# olm-ec-periph.net
KiCad netlist of a schematic drawn in EAGLE
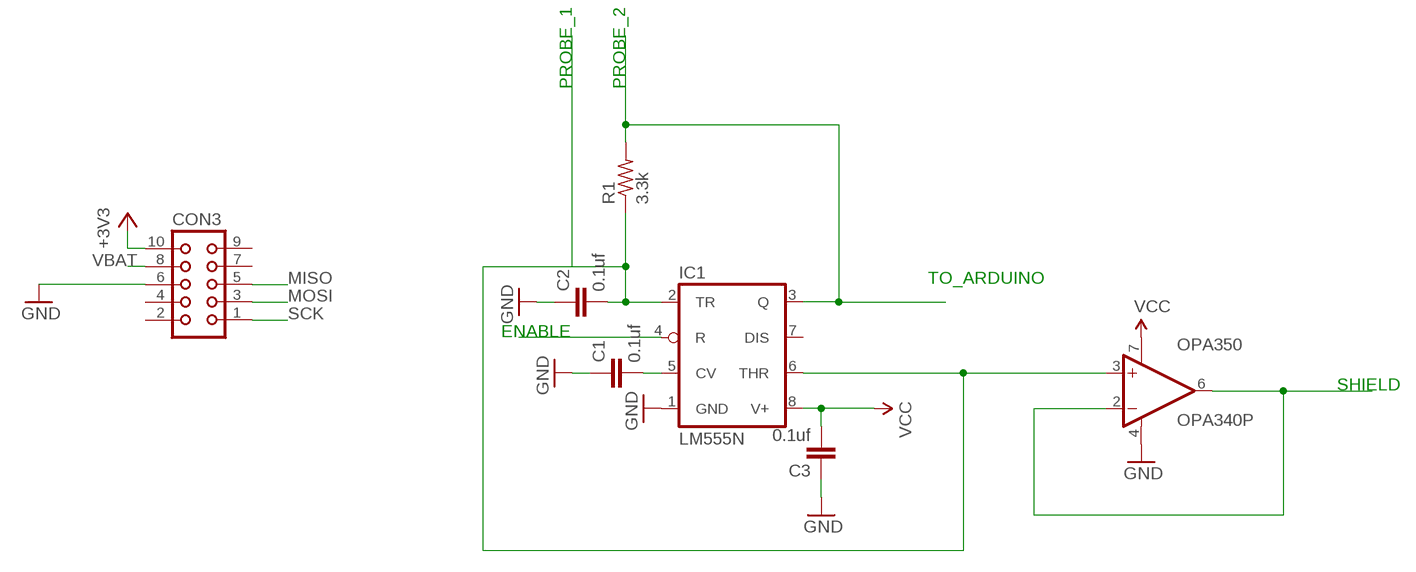
[diagram p0: schematic, sheet 1]

(export (version "E")
  (design (tool "Eeschema 10.0.6"))
  (components
    (comp (ref "C1")
      (value "0.1uf")
      (footprint "eagle-import:C025-025X050")
      (libsource (lib "eagle-import") (part "C-EU025-025X050"))
    )
    (comp (ref "C2")
      (value "0.1uf")
      (footprint "eagle-import:C025-025X050")
      (libsource (lib "eagle-import") (part "C-EU025-025X050"))
    )
    (comp (ref "C3")
      (value "0.1uf")
      (footprint "eagle-import:C025-025X050")
      (libsource (lib "eagle-import") (part "C-EU025-025X050"))
    )
    (comp (ref "CON3")
      (value "CON10")
      (footprint "eagle-import:CON10")
      (libsource (lib "eagle-import") (part "CON10"))
    )
    (comp (ref "IC1")
      (value "LM555N")
      (footprint "eagle-import:DIL08")
      (libsource (lib "eagle-import") (part "555NLM"))
    )
    (comp (ref "OPA350")
      (value "OPA340P")
      (footprint "eagle-import:DIL08")
      (libsource (lib "eagle-import") (part "OPA340P"))
    )
    (comp (ref "R1")
      (value "3.3k")
      (footprint "eagle-import:0207_10")
      (libsource (lib "eagle-import") (part "R-US_0207/10"))
    )
  )
  (nets
    (net (code "1") (name "+3V3") (class "Default")
      (node (ref "CON3") (pin "10") (pinfunction "10_10") (pintype "passive"))
    )
    (net (code "2") (name "/MISO") (class "Default")
      (node (ref "CON3") (pin "5") (pinfunction "5_5") (pintype "passive"))
    )
    (net (code "3") (name "/MOSI") (class "Default")
      (node (ref "CON3") (pin "3") (pinfunction "3_3") (pintype "passive"))
    )
    (net (code "4") (name "/SCK") (class "Default")
      (node (ref "CON3") (pin "1") (pinfunction "1_1") (pintype "passive"))
    )
    (net (code "5") (name "/VBAT") (class "Default")
      (node (ref "CON3") (pin "8") (pinfunction "8_8") (pintype "passive"))
    )
    (net (code "6") (name "GND") (class "Default")
      (node (ref "C1") (pin "1") (pinfunction "1_1") (pintype "passive"))
      (node (ref "C2") (pin "1") (pinfunction "1_1") (pintype "passive"))
      (node (ref "C3") (pin "1") (pinfunction "1_1") (pintype "passive"))
      (node (ref "CON3") (pin "6") (pinfunction "6_6") (pintype "passive"))
      (node (ref "IC1") (pin "1") (pinfunction "GND_1") (pintype "power_in"))
      (node (ref "OPA350") (pin "4") (pinfunction "V-_4") (pintype "power_in"))
    )
    (net (code "7") (name "Net-(IC1-CV)") (class "Default")
      (node (ref "C1") (pin "2") (pinfunction "2_2") (pintype "passive"))
      (node (ref "IC1") (pin "5") (pinfunction "CV_5") (pintype "input"))
    )
    (net (code "8") (name "Net-(IC1-Q)") (class "Default")
      (node (ref "IC1") (pin "3") (pinfunction "Q_3") (pintype "output"))
      (node (ref "R1") (pin "2") (pinfunction "2_2") (pintype "passive"))
    )
    (net (code "9") (name "Net-(IC1-THR)") (class "Default")
      (node (ref "C2") (pin "2") (pinfunction "2_2") (pintype "passive"))
      (node (ref "IC1") (pin "2") (pinfunction "TR_2") (pintype "input"))
      (node (ref "IC1") (pin "6") (pinfunction "THR_6") (pintype "input"))
      (node (ref "OPA350") (pin "3") (pinfunction "+IN_3") (pintype "input"))
      (node (ref "R1") (pin "1") (pinfunction "1_1") (pintype "passive"))
    )
    (net (code "10") (name "Net-(OPA350--IN)") (class "Default")
      (node (ref "OPA350") (pin "2") (pinfunction "-IN_2") (pintype "input"))
      (node (ref "OPA350") (pin "6") (pinfunction "OUT_6") (pintype "output"))
    )
    (net (code "11") (name "VCC") (class "Default")
      (node (ref "C3") (pin "2") (pinfunction "2_2") (pintype "passive"))
      (node (ref "IC1") (pin "8") (pinfunction "V+_8") (pintype "power_in"))
      (node (ref "OPA350") (pin "7") (pinfunction "V+_7") (pintype "power_in"))
    )
    (net (code "12") (name "unconnected-(CON3-Pad2)") (class "Default")
      (node (ref "CON3") (pin "2") (pinfunction "2_2") (pintype "passive"))
    )
    (net (code "13") (name "unconnected-(CON3-Pad4)") (class "Default")
      (node (ref "CON3") (pin "4") (pinfunction "4_4") (pintype "passive"))
    )
    (net (code "14") (name "unconnected-(CON3-Pad7)") (class "Default")
      (node (ref "CON3") (pin "7") (pinfunction "7_7") (pintype "passive"))
    )
    (net (code "15") (name "unconnected-(CON3-Pad9)") (class "Default")
      (node (ref "CON3") (pin "9") (pinfunction "9_9") (pintype "passive"))
    )
    (net (code "16") (name "unconnected-(IC1-DIS-Pad7)") (class "Default")
      (node (ref "IC1") (pin "7") (pinfunction "DIS_7") (pintype "input"))
    )
    (net (code "17") (name "unconnected-(IC1-R-Pad4)") (class "Default")
      (node (ref "IC1") (pin "4") (pinfunction "R_4") (pintype "input"))
    )
  )
)
